# sofi_v7_main_rev2_2.net
KiCad netlist of a schematic drawn in EAGLE
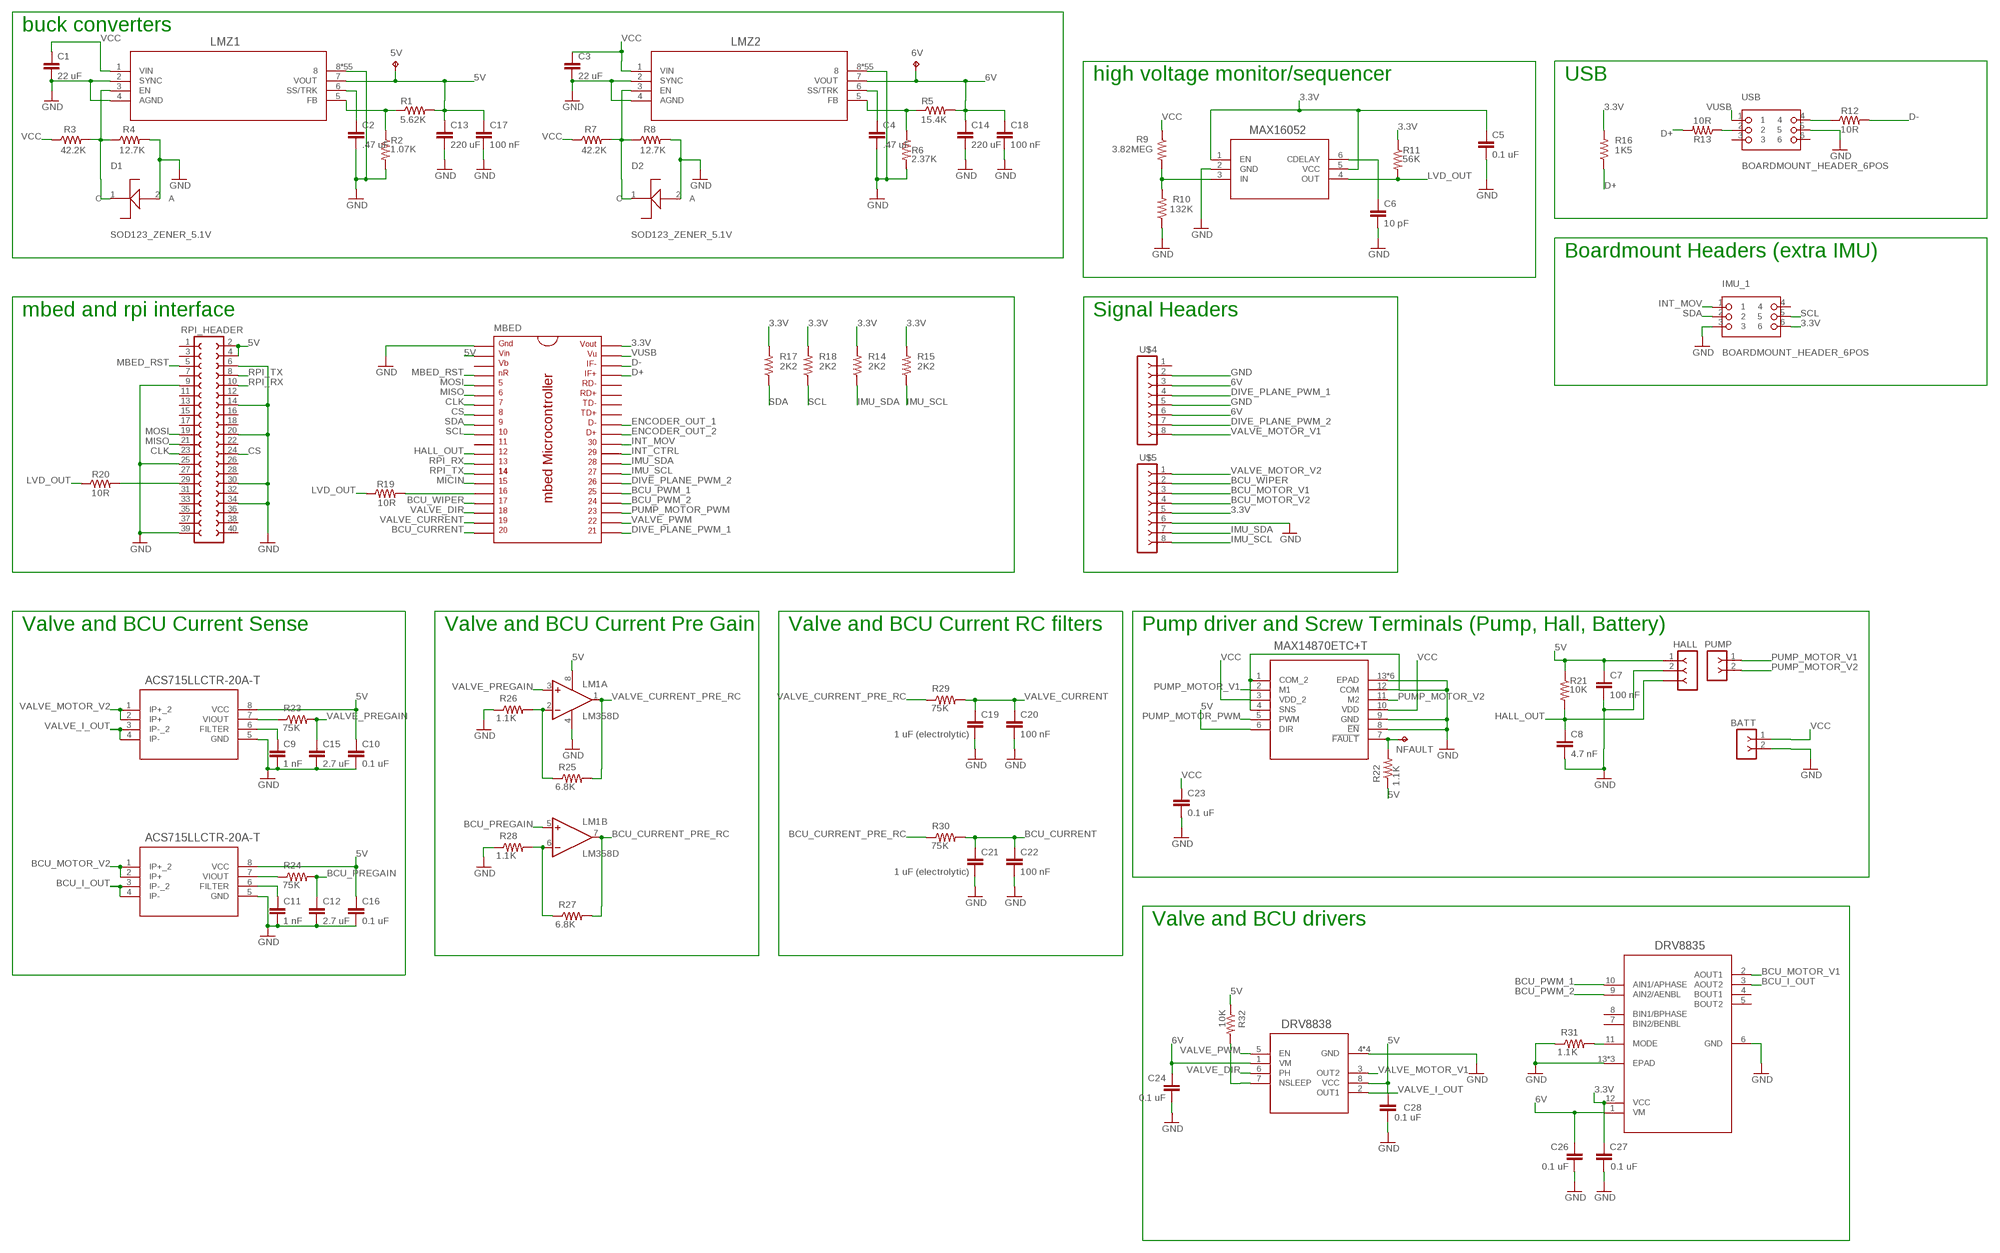
[diagram p0: schematic, sheet 1]

(export (version "E")
  (design (tool "Eeschema 10.0.6"))
  (components
    (comp (ref "5V")
      (value "TPB1,27")
      (footprint "eagle-import:B1,27")
      (libsource (lib "eagle-import") (part "TPB1,27"))
    )
    (comp (ref "6V")
      (value "TPB1,27")
      (footprint "eagle-import:B1,27")
      (libsource (lib "eagle-import") (part "TPB1,27"))
    )
    (comp (ref "ACS715_BCU")
      (value "ACS715LLCTR-20A-T")
      (footprint "eagle-import:SOIC-8")
      (fields (field (name "MANUFACTURER_PART_NUMBER") "ACS715LLCTR20AT"))
      (libsource (lib "eagle-import") (part "ACS715LLCTR-20A-T"))
    )
    (comp (ref "ACS715_VALVE")
      (value "ACS715LLCTR-20A-T")
      (footprint "eagle-import:SOIC-8")
      (fields (field (name "MANUFACTURER_PART_NUMBER") "ACS715LLCTR20AT"))
      (libsource (lib "eagle-import") (part "ACS715LLCTR-20A-T"))
    )
    (comp (ref "BATT")
      (value "2POS_BLOCK2POS_BLOCK_NOSTANDS")
      (footprint "eagle-import:2POS_BLOCK_NOSTANDS")
      (libsource (lib "eagle-import") (part "2POS_BLOCK2POS_BLOCK_NOSTANDS"))
    )
    (comp (ref "C1")
      (value "22 uF")
      (footprint "eagle-import:C0805")
      (libsource (lib "eagle-import") (part "C-EUC0805"))
    )
    (comp (ref "C2")
      (value ".47 uF")
      (footprint "eagle-import:C0805")
      (libsource (lib "eagle-import") (part "C-EUC0805"))
    )
    (comp (ref "C3")
      (value "22 uF")
      (footprint "eagle-import:C0805")
      (libsource (lib "eagle-import") (part "C-EUC0805"))
    )
    (comp (ref "C4")
      (value ".47 uF")
      (footprint "eagle-import:C0805")
      (libsource (lib "eagle-import") (part "C-EUC0805"))
    )
    (comp (ref "C5")
      (value "0.1 uF")
      (footprint "eagle-import:C0805")
      (libsource (lib "eagle-import") (part "C-EUC0805"))
    )
    (comp (ref "C6")
      (value "10 pF")
      (footprint "eagle-import:C0603")
      (libsource (lib "eagle-import") (part "C-EUC0603"))
    )
    (comp (ref "C7")
      (value "100 nF")
      (footprint "eagle-import:C0805")
      (libsource (lib "eagle-import") (part "C-EUC0805"))
    )
    (comp (ref "C8")
      (value "4.7 nF")
      (footprint "eagle-import:C0805")
      (libsource (lib "eagle-import") (part "C-EUC0805"))
    )
    (comp (ref "C9")
      (value "1 nF")
      (footprint "eagle-import:C0603")
      (libsource (lib "eagle-import") (part "C-EUC0603"))
    )
    (comp (ref "C10")
      (value "0.1 uF")
      (footprint "eagle-import:C0603")
      (libsource (lib "eagle-import") (part "C-EUC0603"))
    )
    (comp (ref "C11")
      (value "1 nF")
      (footprint "eagle-import:C0603")
      (libsource (lib "eagle-import") (part "C-EUC0603"))
    )
    (comp (ref "C12")
      (value "2.7 uF")
      (footprint "eagle-import:C0603")
      (libsource (lib "eagle-import") (part "C-EUC0603"))
    )
    (comp (ref "C13")
      (value "220 uF")
      (footprint "eagle-import:C1206")
      (libsource (lib "eagle-import") (part "resistor_C-EUC1206"))
    )
    (comp (ref "C14")
      (value "220 uF")
      (footprint "eagle-import:C1206")
      (libsource (lib "eagle-import") (part "resistor_C-EUC1206"))
    )
    (comp (ref "C15")
      (value "2.7 uF")
      (footprint "eagle-import:C0603")
      (libsource (lib "eagle-import") (part "C-EUC0603"))
    )
    (comp (ref "C16")
      (value "0.1 uF")
      (footprint "eagle-import:C0603")
      (libsource (lib "eagle-import") (part "C-EUC0603"))
    )
    (comp (ref "C17")
      (value "100 nF")
      (footprint "eagle-import:C0805")
      (libsource (lib "eagle-import") (part "C-EUC0805"))
    )
    (comp (ref "C18")
      (value "100 nF")
      (footprint "eagle-import:C0805")
      (libsource (lib "eagle-import") (part "C-EUC0805"))
    )
    (comp (ref "C19")
      (value "1 uF (electrolytic)")
      (footprint "eagle-import:C0603")
      (libsource (lib "eagle-import") (part "C-EUC0603"))
    )
    (comp (ref "C20")
      (value "100 nF")
      (footprint "eagle-import:C0805")
      (libsource (lib "eagle-import") (part "C-EUC0805"))
    )
    (comp (ref "C21")
      (value "1 uF (electrolytic)")
      (footprint "eagle-import:C0603")
      (libsource (lib "eagle-import") (part "C-EUC0603"))
    )
    (comp (ref "C22")
      (value "100 nF")
      (footprint "eagle-import:C0805")
      (libsource (lib "eagle-import") (part "C-EUC0805"))
    )
    (comp (ref "C23")
      (value "0.1 uF")
      (footprint "eagle-import:C0805")
      (libsource (lib "eagle-import") (part "C-EUC0805"))
    )
    (comp (ref "C24")
      (value "0.1 uF")
      (footprint "eagle-import:C0603")
      (libsource (lib "eagle-import") (part "C-EUC0603"))
    )
    (comp (ref "C26")
      (value "0.1 uF")
      (footprint "eagle-import:C0603")
      (libsource (lib "eagle-import") (part "C-EUC0603"))
    )
    (comp (ref "C27")
      (value "0.1 uF")
      (footprint "eagle-import:C0603")
      (libsource (lib "eagle-import") (part "C-EUC0603"))
    )
    (comp (ref "C28")
      (value "0.1 uF")
      (footprint "eagle-import:C0603")
      (libsource (lib "eagle-import") (part "C-EUC0603"))
    )
    (comp (ref "D1")
      (value "SOD123_ZENER_5.1V")
      (footprint "eagle-import:SOD123_ZENER")
      (libsource (lib "eagle-import") (part "SOD123_ZENER_5.1V"))
    )
    (comp (ref "D2")
      (value "SOD123_ZENER_5.1V")
      (footprint "eagle-import:SOD123_ZENER")
      (libsource (lib "eagle-import") (part "SOD123_ZENER_5.1V"))
    )
    (comp (ref "DRV8835")
      (value "DRV8835DSSRDSS12_P9X2_THERMAL_EXTENDED")
      (footprint "eagle-import:DSS12_P9X2_THERMAL_EXTENDED")
      (libsource (lib "eagle-import") (part "DRV8835DSSRDSS12_P9X2_THERMAL_EXTENDED"))
    )
    (comp (ref "DRV8838")
      (value "DRV8838DSGTDSG8_P9X1P6_THERMAL_EXTENDED")
      (footprint "eagle-import:DSG8_P9X1P6_THERMAL_EXTENDED")
      (libsource (lib "eagle-import") (part "DRV8838DSGTDSG8_P9X1P6_THERMAL_EXTENDED"))
    )
    (comp (ref "HALL")
      (value "3POS_TERMINAL")
      (footprint "eagle-import:3POS_TERMINAL")
      (libsource (lib "eagle-import") (part "3POS_TERMINAL"))
    )
    (comp (ref "IMU_1")
      (value "BOARDMOUNT_HEADER_6POS")
      (footprint "eagle-import:BOARDMOUNT_HEADER")
      (libsource (lib "eagle-import") (part "BOARDMOUNT_HEADER_6POS"))
    )
    (comp (ref "LM1")
      (value "LM358D")
      (footprint "eagle-import:SO08")
      (libsource (lib "eagle-import") (part "LM358D"))
    )
    (comp (ref "LMZ1")
      (value "LMZ23605TZE/NOPBTZA07A_THERMAL_TABBED")
      (footprint "eagle-import:TZA07A_THERMAL_TABBED")
      (libsource (lib "eagle-import") (part "LMZ23605TZE/NOPBTZA07A_THERMAL_TABBED"))
    )
    (comp (ref "LMZ2")
      (value "LMZ23605TZE/NOPBTZA07A_THERMAL_TABBED")
      (footprint "eagle-import:TZA07A_THERMAL_TABBED")
      (libsource (lib "eagle-import") (part "LMZ23605TZE/NOPBTZA07A_THERMAL_TABBED"))
    )
    (comp (ref "MAX14870")
      (value "MAX14870ETC+T")
      (footprint "eagle-import:21-0664B")
      (fields (field (name "COPYRIGHT") "Copyright (C) 2018 Accelerated Designs. All rights reserved"))
      (libsource (lib "eagle-import") (part "MAX14870ETC+T"))
    )
    (comp (ref "MAX16052")
      (value "MAX16052AUT+T")
      (footprint "eagle-import:21-0058I")
      (fields (field (name "MANUFACTURER_PART_NUMBER") "max16052aut+t"))
      (libsource (lib "eagle-import") (part "MAX16052AUT+T"))
    )
    (comp (ref "MBED")
      (value "MBED_MICROCONTROLLER")
      (footprint "eagle-import:DIL40_0.9")
      (libsource (lib "eagle-import") (part "MBED_MICROCONTROLLER"))
    )
    (comp (ref "NFAULT")
      (value "TPB1,27")
      (footprint "eagle-import:B1,27")
      (libsource (lib "eagle-import") (part "TPB1,27"))
    )
    (comp (ref "PUMP")
      (value "2POS_BLOCK2POS_BLOCK_NOSTANDS")
      (footprint "eagle-import:2POS_BLOCK_NOSTANDS")
      (libsource (lib "eagle-import") (part "2POS_BLOCK2POS_BLOCK_NOSTANDS"))
    )
    (comp (ref "R1")
      (value "5.62K")
      (footprint "eagle-import:M0805")
      (libsource (lib "eagle-import") (part "R-US_M0805"))
    )
    (comp (ref "R2")
      (value "1.07K")
      (footprint "eagle-import:M0805")
      (libsource (lib "eagle-import") (part "R-US_M0805"))
    )
    (comp (ref "R3")
      (value "42.2K")
      (footprint "eagle-import:M0805")
      (libsource (lib "eagle-import") (part "R-US_M0805"))
    )
    (comp (ref "R4")
      (value "12.7K")
      (footprint "eagle-import:M0805")
      (libsource (lib "eagle-import") (part "R-US_M0805"))
    )
    (comp (ref "R5")
      (value "15.4K")
      (footprint "eagle-import:M0805")
      (libsource (lib "eagle-import") (part "R-US_M0805"))
    )
    (comp (ref "R6")
      (value "2.37K")
      (footprint "eagle-import:M0805")
      (libsource (lib "eagle-import") (part "R-US_M0805"))
    )
    (comp (ref "R7")
      (value "42.2K")
      (footprint "eagle-import:M0805")
      (libsource (lib "eagle-import") (part "R-US_M0805"))
    )
    (comp (ref "R8")
      (value "12.7K")
      (footprint "eagle-import:M0805")
      (libsource (lib "eagle-import") (part "R-US_M0805"))
    )
    (comp (ref "R9")
      (value "3.82MEG")
      (footprint "eagle-import:0603")
      (libsource (lib "eagle-import") (part "RESISTOR0603"))
    )
    (comp (ref "R10")
      (value "132K")
      (footprint "eagle-import:0603")
      (libsource (lib "eagle-import") (part "RESISTOR0603"))
    )
    (comp (ref "R11")
      (value "56K")
      (footprint "eagle-import:R0603")
      (libsource (lib "eagle-import") (part "R-US_R0603"))
    )
    (comp (ref "R12")
      (value "10R")
      (footprint "eagle-import:0603")
      (libsource (lib "eagle-import") (part "RESISTOR0603"))
    )
    (comp (ref "R13")
      (value "10R")
      (footprint "eagle-import:0603")
      (libsource (lib "eagle-import") (part "RESISTOR0603"))
    )
    (comp (ref "R14")
      (value "2K2")
      (footprint "eagle-import:0603")
      (libsource (lib "eagle-import") (part "RESISTOR0603"))
    )
    (comp (ref "R15")
      (value "2K2")
      (footprint "eagle-import:0603")
      (libsource (lib "eagle-import") (part "RESISTOR0603"))
    )
    (comp (ref "R16")
      (value "1K5")
      (footprint "eagle-import:0603")
      (libsource (lib "eagle-import") (part "RESISTOR0603"))
    )
    (comp (ref "R17")
      (value "2K2")
      (footprint "eagle-import:0603")
      (libsource (lib "eagle-import") (part "RESISTOR0603"))
    )
    (comp (ref "R18")
      (value "2K2")
      (footprint "eagle-import:0603")
      (libsource (lib "eagle-import") (part "RESISTOR0603"))
    )
    (comp (ref "R19")
      (value "10R")
      (footprint "eagle-import:0603")
      (libsource (lib "eagle-import") (part "RESISTOR0603"))
    )
    (comp (ref "R20")
      (value "10R")
      (footprint "eagle-import:0603")
      (libsource (lib "eagle-import") (part "RESISTOR0603"))
    )
    (comp (ref "R21")
      (value "10K")
      (footprint "eagle-import:M0805")
      (libsource (lib "eagle-import") (part "R-US_M0805"))
    )
    (comp (ref "R22")
      (value "1.1K")
      (footprint "eagle-import:M0805")
      (libsource (lib "eagle-import") (part "R-US_M0805"))
    )
    (comp (ref "R23")
      (value "75K")
      (footprint "eagle-import:M0805")
      (libsource (lib "eagle-import") (part "R-US_M0805"))
    )
    (comp (ref "R24")
      (value "75K")
      (footprint "eagle-import:M0805")
      (libsource (lib "eagle-import") (part "R-US_M0805"))
    )
    (comp (ref "R25")
      (value "6.8K")
      (footprint "eagle-import:M0805")
      (libsource (lib "eagle-import") (part "R-US_M0805"))
    )
    (comp (ref "R26")
      (value "1.1K")
      (footprint "eagle-import:M0805")
      (libsource (lib "eagle-import") (part "R-US_M0805"))
    )
    (comp (ref "R27")
      (value "6.8K")
      (footprint "eagle-import:M0805")
      (libsource (lib "eagle-import") (part "R-US_M0805"))
    )
    (comp (ref "R28")
      (value "1.1K")
      (footprint "eagle-import:M0805")
      (libsource (lib "eagle-import") (part "R-US_M0805"))
    )
    (comp (ref "R29")
      (value "75K")
      (footprint "eagle-import:M0805")
      (libsource (lib "eagle-import") (part "R-US_M0805"))
    )
    (comp (ref "R30")
      (value "75K")
      (footprint "eagle-import:M0805")
      (libsource (lib "eagle-import") (part "R-US_M0805"))
    )
    (comp (ref "R31")
      (value "1.1K")
      (footprint "eagle-import:M0805")
      (libsource (lib "eagle-import") (part "R-US_M0805"))
    )
    (comp (ref "R32")
      (value "10K")
      (footprint "eagle-import:M0805")
      (libsource (lib "eagle-import") (part "R-US_M0805"))
    )
    (comp (ref "RPI_HEADER")
      (value "FE20-2")
      (footprint "eagle-import:FE20-2")
      (libsource (lib "eagle-import") (part "FE20-2"))
    )
    (comp (ref "U$4")
      (value "8POS_TERMINAL")
      (footprint "eagle-import:8POS_TERMINAL")
      (libsource (lib "eagle-import") (part "8POS_TERMINAL"))
    )
    (comp (ref "U$5")
      (value "8POS_TERMINAL")
      (footprint "eagle-import:8POS_TERMINAL")
      (libsource (lib "eagle-import") (part "8POS_TERMINAL"))
    )
    (comp (ref "USB")
      (value "BOARDMOUNT_HEADER_6POS")
      (footprint "eagle-import:BOARDMOUNT_HEADER")
      (libsource (lib "eagle-import") (part "BOARDMOUNT_HEADER_6POS"))
    )
  )
  (nets
    (net (code "1") (name "/3.3V") (class "Default")
      (node (ref "C27") (pin "1") (pinfunction "1_1") (pintype "passive"))
      (node (ref "C5") (pin "1") (pinfunction "1_1") (pintype "passive"))
      (node (ref "DRV8835") (pin "12") (pinfunction "VCC_12") (pintype "power_in"))
      (node (ref "IMU_1") (pin "6") (pinfunction "6_6") (pintype "bidirectional"))
      (node (ref "MAX16052") (pin "1") (pinfunction "EN_1") (pintype "input"))
      (node (ref "MAX16052") (pin "5") (pinfunction "VCC_5") (pintype "power_in"))
      (node (ref "MBED") (pin "40") (pinfunction "P$40_40") (pintype "bidirectional"))
      (node (ref "R11") (pin "1") (pinfunction "1_1") (pintype "passive"))
      (node (ref "R14") (pin "2") (pinfunction "2_2") (pintype "passive"))
      (node (ref "R15") (pin "2") (pinfunction "2_2") (pintype "passive"))
      (node (ref "R16") (pin "2") (pinfunction "2_2") (pintype "passive"))
      (node (ref "R17") (pin "2") (pinfunction "2_2") (pintype "passive"))
      (node (ref "R18") (pin "2") (pinfunction "2_2") (pintype "passive"))
      (node (ref "U$5") (pin "5") (pinfunction "5_5") (pintype "passive"))
    )
    (net (code "2") (name "/5V") (class "Default")
      (node (ref "5V") (pin "TP") (pinfunction "TP_TP") (pintype "input"))
      (node (ref "ACS715_BCU") (pin "8") (pinfunction "VCC_8") (pintype "power_in"))
      (node (ref "ACS715_VALVE") (pin "8") (pinfunction "VCC_8") (pintype "power_in"))
      (node (ref "C10") (pin "1") (pinfunction "1_1") (pintype "passive"))
      (node (ref "C13") (pin "1") (pinfunction "1_1") (pintype "passive"))
      (node (ref "C16") (pin "1") (pinfunction "1_1") (pintype "passive"))
      (node (ref "C17") (pin "1") (pinfunction "1_1") (pintype "passive"))
      (node (ref "C28") (pin "1") (pinfunction "1_1") (pintype "passive"))
      (node (ref "C7") (pin "1") (pinfunction "1_1") (pintype "passive"))
      (node (ref "DRV8838") (pin "8") (pinfunction "VCC_8") (pintype "power_in"))
      (node (ref "HALL") (pin "1") (pinfunction "1_1") (pintype "passive"))
      (node (ref "LM1") (pin "8") (pinfunction "V+_8") (pintype "power_in"))
      (node (ref "LMZ1") (pin "7") (pinfunction "VOUT_7") (pintype "output"))
      (node (ref "MAX14870") (pin "6") (pinfunction "DIR_6") (pintype "passive"))
      (node (ref "MBED") (pin "2") (pinfunction "P$2_2") (pintype "bidirectional"))
      (node (ref "R1") (pin "2") (pinfunction "2_2") (pintype "passive"))
      (node (ref "R21") (pin "1") (pinfunction "1_1") (pintype "passive"))
      (node (ref "R22") (pin "1") (pinfunction "1_1") (pintype "passive"))
      (node (ref "R32") (pin "1") (pinfunction "1_1") (pintype "passive"))
      (node (ref "RPI_HEADER") (pin "2") (pinfunction "2_2") (pintype "passive"))
      (node (ref "RPI_HEADER") (pin "4") (pinfunction "4_4") (pintype "passive"))
    )
    (net (code "3") (name "/6V") (class "Default")
      (node (ref "6V") (pin "TP") (pinfunction "TP_TP") (pintype "input"))
      (node (ref "C14") (pin "1") (pinfunction "1_1") (pintype "passive"))
      (node (ref "C18") (pin "1") (pinfunction "1_1") (pintype "passive"))
      (node (ref "C24") (pin "1") (pinfunction "1_1") (pintype "passive"))
      (node (ref "C26") (pin "1") (pinfunction "1_1") (pintype "passive"))
      (node (ref "DRV8835") (pin "1") (pinfunction "VM_1") (pintype "power_in"))
      (node (ref "DRV8838") (pin "1") (pinfunction "VM_1") (pintype "power_in"))
      (node (ref "LMZ2") (pin "7") (pinfunction "VOUT_7") (pintype "output"))
      (node (ref "R5") (pin "2") (pinfunction "2_2") (pintype "passive"))
      (node (ref "U$4") (pin "3") (pinfunction "3_3") (pintype "passive"))
      (node (ref "U$4") (pin "6") (pinfunction "6_6") (pintype "passive"))
    )
    (net (code "4") (name "/BCU_CURRENT") (class "Default")
      (node (ref "C21") (pin "1") (pinfunction "1_1") (pintype "passive"))
      (node (ref "C22") (pin "1") (pinfunction "1_1") (pintype "passive"))
      (node (ref "MBED") (pin "20") (pinfunction "P$20_20") (pintype "bidirectional"))
      (node (ref "R30") (pin "2") (pinfunction "2_2") (pintype "passive"))
    )
    (net (code "5") (name "/BCU_CURRENT_PRE_RC") (class "Default")
      (node (ref "LM1") (pin "7") (pinfunction "OUT_7") (pintype "output"))
      (node (ref "R27") (pin "2") (pinfunction "2_2") (pintype "passive"))
      (node (ref "R30") (pin "1") (pinfunction "1_1") (pintype "passive"))
    )
    (net (code "6") (name "/BCU_I_OUT") (class "Default")
      (node (ref "ACS715_BCU") (pin "3") (pinfunction "IP-_2_3") (pintype "output"))
      (node (ref "ACS715_BCU") (pin "4") (pinfunction "IP-_4") (pintype "output"))
      (node (ref "DRV8835") (pin "3") (pinfunction "AOUT2_3") (pintype "output"))
    )
    (net (code "7") (name "/BCU_MOTOR_V1") (class "Default")
      (node (ref "DRV8835") (pin "2") (pinfunction "AOUT1_2") (pintype "output"))
      (node (ref "U$5") (pin "3") (pinfunction "3_3") (pintype "passive"))
    )
    (net (code "8") (name "/BCU_MOTOR_V2") (class "Default")
      (node (ref "ACS715_BCU") (pin "1") (pinfunction "IP+_2_1") (pintype "input"))
      (node (ref "ACS715_BCU") (pin "2") (pinfunction "IP+_2") (pintype "input"))
      (node (ref "U$5") (pin "4") (pinfunction "4_4") (pintype "passive"))
    )
    (net (code "9") (name "/BCU_PREGAIN") (class "Default")
      (node (ref "C12") (pin "1") (pinfunction "1_1") (pintype "passive"))
      (node (ref "LM1") (pin "5") (pinfunction "+IN_5") (pintype "input"))
      (node (ref "R24") (pin "2") (pinfunction "2_2") (pintype "passive"))
    )
    (net (code "10") (name "/BCU_PWM_1") (class "Default")
      (node (ref "DRV8835") (pin "10") (pinfunction "AIN1/APHASE_10") (pintype "input"))
      (node (ref "MBED") (pin "25") (pinfunction "P$25_25") (pintype "bidirectional"))
    )
    (net (code "11") (name "/BCU_PWM_2") (class "Default")
      (node (ref "DRV8835") (pin "9") (pinfunction "AIN2/AENBL_9") (pintype "input"))
      (node (ref "MBED") (pin "24") (pinfunction "P$24_24") (pintype "bidirectional"))
    )
    (net (code "12") (name "/BCU_WIPER") (class "Default")
      (node (ref "MBED") (pin "17") (pinfunction "P$17_17") (pintype "bidirectional"))
      (node (ref "U$5") (pin "2") (pinfunction "2_2") (pintype "passive"))
    )
    (net (code "13") (name "/CLK") (class "Default")
      (node (ref "MBED") (pin "7") (pinfunction "P$7_7") (pintype "bidirectional"))
      (node (ref "RPI_HEADER") (pin "23") (pinfunction "23_23") (pintype "passive"))
    )
    (net (code "14") (name "/CS") (class "Default")
      (node (ref "MBED") (pin "8") (pinfunction "P$8_8") (pintype "bidirectional"))
      (node (ref "RPI_HEADER") (pin "24") (pinfunction "24_24") (pintype "passive"))
    )
    (net (code "15") (name "/D+") (class "Default")
      (node (ref "MBED") (pin "37") (pinfunction "P$37_37") (pintype "bidirectional"))
      (node (ref "R13") (pin "2") (pinfunction "2_2") (pintype "passive"))
      (node (ref "R16") (pin "1") (pinfunction "1_1") (pintype "passive"))
    )
    (net (code "16") (name "/D-") (class "Default")
      (node (ref "MBED") (pin "38") (pinfunction "P$38_38") (pintype "bidirectional"))
      (node (ref "R12") (pin "2") (pinfunction "2_2") (pintype "passive"))
    )
    (net (code "17") (name "/DIVE_PLANE_PWM_1") (class "Default")
      (node (ref "MBED") (pin "21") (pinfunction "P$21_21") (pintype "bidirectional"))
      (node (ref "U$4") (pin "4") (pinfunction "4_4") (pintype "passive"))
    )
    (net (code "18") (name "/DIVE_PLANE_PWM_2") (class "Default")
      (node (ref "MBED") (pin "26") (pinfunction "P$26_26") (pintype "bidirectional"))
      (node (ref "U$4") (pin "7") (pinfunction "7_7") (pintype "passive"))
    )
    (net (code "19") (name "/ENCODER_OUT_1") (class "Default")
      (node (ref "MBED") (pin "32") (pinfunction "P$32_32") (pintype "bidirectional"))
    )
    (net (code "20") (name "/ENCODER_OUT_2") (class "Default")
      (node (ref "MBED") (pin "31") (pinfunction "P$31_31") (pintype "bidirectional"))
    )
    (net (code "21") (name "/HALL_OUT") (class "Default")
      (node (ref "C8") (pin "1") (pinfunction "1_1") (pintype "passive"))
      (node (ref "HALL") (pin "3") (pinfunction "3_3") (pintype "passive"))
      (node (ref "MBED") (pin "12") (pinfunction "P$12_12") (pintype "bidirectional"))
      (node (ref "R21") (pin "2") (pinfunction "2_2") (pintype "passive"))
    )
    (net (code "22") (name "/IMU_SCL") (class "Default")
      (node (ref "MBED") (pin "27") (pinfunction "P$27_27") (pintype "bidirectional"))
      (node (ref "R15") (pin "1") (pinfunction "1_1") (pintype "passive"))
      (node (ref "U$5") (pin "8") (pinfunction "8_8") (pintype "passive"))
    )
    (net (code "23") (name "/IMU_SDA") (class "Default")
      (node (ref "MBED") (pin "28") (pinfunction "P$28_28") (pintype "bidirectional"))
      (node (ref "R14") (pin "1") (pinfunction "1_1") (pintype "passive"))
      (node (ref "U$5") (pin "7") (pinfunction "7_7") (pintype "passive"))
    )
    (net (code "24") (name "/INT_CTRL") (class "Default")
      (node (ref "MBED") (pin "29") (pinfunction "P$29_29") (pintype "bidirectional"))
    )
    (net (code "25") (name "/INT_MOV") (class "Default")
      (node (ref "IMU_1") (pin "1") (pinfunction "1_1") (pintype "bidirectional"))
      (node (ref "MBED") (pin "30") (pinfunction "P$30_30") (pintype "bidirectional"))
    )
    (net (code "26") (name "/LVD_OUT") (class "Default")
      (node (ref "MAX16052") (pin "4") (pinfunction "OUT_4") (pintype "output"))
      (node (ref "R11") (pin "2") (pinfunction "2_2") (pintype "passive"))
      (node (ref "R19") (pin "1") (pinfunction "1_1") (pintype "passive"))
      (node (ref "R20") (pin "1") (pinfunction "1_1") (pintype "passive"))
    )
    (net (code "27") (name "/MBED_RST") (class "Default")
      (node (ref "MBED") (pin "4") (pinfunction "P$4_4") (pintype "bidirectional"))
      (node (ref "RPI_HEADER") (pin "5") (pinfunction "5_5") (pintype "passive"))
    )
    (net (code "28") (name "/MICIN") (class "Default")
      (node (ref "MBED") (pin "15") (pinfunction "P$15_15") (pintype "bidirectional"))
    )
    (net (code "29") (name "/MISO") (class "Default")
      (node (ref "MBED") (pin "6") (pinfunction "P$6_6") (pintype "bidirectional"))
      (node (ref "RPI_HEADER") (pin "21") (pinfunction "21_21") (pintype "passive"))
    )
    (net (code "30") (name "/MOSI") (class "Default")
      (node (ref "MBED") (pin "5") (pinfunction "P$5_5") (pintype "bidirectional"))
      (node (ref "RPI_HEADER") (pin "19") (pinfunction "19_19") (pintype "passive"))
    )
    (net (code "31") (name "/PUMP_MOTOR_PWM") (class "Default")
      (node (ref "MAX14870") (pin "5") (pinfunction "PWM_5") (pintype "passive"))
      (node (ref "MBED") (pin "23") (pinfunction "P$23_23") (pintype "bidirectional"))
    )
    (net (code "32") (name "/PUMP_MOTOR_V1") (class "Default")
      (node (ref "MAX14870") (pin "2") (pinfunction "M1_2") (pintype "bidirectional"))
      (node (ref "PUMP") (pin "1") (pinfunction "1_1") (pintype "passive"))
    )
    (net (code "33") (name "/PUMP_MOTOR_V2") (class "Default")
      (node (ref "MAX14870") (pin "11") (pinfunction "M2_11") (pintype "bidirectional"))
      (node (ref "PUMP") (pin "2") (pinfunction "2_2") (pintype "passive"))
    )
    (net (code "34") (name "/RPI_RX") (class "Default")
      (node (ref "MBED") (pin "13") (pinfunction "P$13_13") (pintype "bidirectional"))
      (node (ref "RPI_HEADER") (pin "10") (pinfunction "10_10") (pintype "passive"))
    )
    (net (code "35") (name "/RPI_TX") (class "Default")
      (node (ref "MBED") (pin "14") (pinfunction "P$14_14") (pintype "bidirectional"))
      (node (ref "RPI_HEADER") (pin "8") (pinfunction "8_8") (pintype "passive"))
    )
    (net (code "36") (name "/SCL") (class "Default")
      (node (ref "IMU_1") (pin "5") (pinfunction "5_5") (pintype "bidirectional"))
      (node (ref "MBED") (pin "10") (pinfunction "P$10_10") (pintype "bidirectional"))
      (node (ref "R18") (pin "1") (pinfunction "1_1") (pintype "passive"))
    )
    (net (code "37") (name "/SDA") (class "Default")
      (node (ref "IMU_1") (pin "2") (pinfunction "2_2") (pintype "bidirectional"))
      (node (ref "MBED") (pin "9") (pinfunction "P$9_9") (pintype "bidirectional"))
      (node (ref "R17") (pin "1") (pinfunction "1_1") (pintype "passive"))
    )
    (net (code "38") (name "/VALVE_CURRENT") (class "Default")
      (node (ref "C19") (pin "1") (pinfunction "1_1") (pintype "passive"))
      (node (ref "C20") (pin "1") (pinfunction "1_1") (pintype "passive"))
      (node (ref "MBED") (pin "19") (pinfunction "P$19_19") (pintype "bidirectional"))
      (node (ref "R29") (pin "2") (pinfunction "2_2") (pintype "passive"))
    )
    (net (code "39") (name "/VALVE_CURRENT_PRE_RC") (class "Default")
      (node (ref "LM1") (pin "1") (pinfunction "OUT_1") (pintype "output"))
      (node (ref "R25") (pin "2") (pinfunction "2_2") (pintype "passive"))
      (node (ref "R29") (pin "1") (pinfunction "1_1") (pintype "passive"))
    )
    (net (code "40") (name "/VALVE_DIR") (class "Default")
      (node (ref "DRV8838") (pin "6") (pinfunction "PH_6") (pintype "input"))
      (node (ref "MBED") (pin "18") (pinfunction "P$18_18") (pintype "bidirectional"))
    )
    (net (code "41") (name "/VALVE_I_OUT") (class "Default")
      (node (ref "ACS715_VALVE") (pin "3") (pinfunction "IP-_2_3") (pintype "output"))
      (node (ref "ACS715_VALVE") (pin "4") (pinfunction "IP-_4") (pintype "output"))
      (node (ref "DRV8838") (pin "2") (pinfunction "OUT1_2") (pintype "output"))
    )
    (net (code "42") (name "/VALVE_MOTOR_V1") (class "Default")
      (node (ref "DRV8838") (pin "3") (pinfunction "OUT2_3") (pintype "output"))
      (node (ref "U$4") (pin "8") (pinfunction "8_8") (pintype "passive"))
    )
    (net (code "43") (name "/VALVE_MOTOR_V2") (class "Default")
      (node (ref "ACS715_VALVE") (pin "1") (pinfunction "IP+_2_1") (pintype "input"))
      (node (ref "ACS715_VALVE") (pin "2") (pinfunction "IP+_2") (pintype "input"))
      (node (ref "U$5") (pin "1") (pinfunction "1_1") (pintype "passive"))
    )
    (net (code "44") (name "/VALVE_PREGAIN") (class "Default")
      (node (ref "C15") (pin "1") (pinfunction "1_1") (pintype "passive"))
      (node (ref "LM1") (pin "3") (pinfunction "+IN_3") (pintype "input"))
      (node (ref "R23") (pin "2") (pinfunction "2_2") (pintype "passive"))
    )
    (net (code "45") (name "/VALVE_PWM") (class "Default")
      (node (ref "DRV8838") (pin "5") (pinfunction "EN_5") (pintype "input"))
      (node (ref "MBED") (pin "22") (pinfunction "P$22_22") (pintype "bidirectional"))
    )
    (net (code "46") (name "/VCC") (class "Default")
      (node (ref "BATT") (pin "1") (pinfunction "1_1") (pintype "passive"))
      (node (ref "C1") (pin "1") (pinfunction "1_1") (pintype "passive"))
      (node (ref "C23") (pin "1") (pinfunction "1_1") (pintype "passive"))
      (node (ref "C3") (pin "1") (pinfunction "1_1") (pintype "passive"))
      (node (ref "LMZ1") (pin "1") (pinfunction "VIN_1") (pintype "input"))
      (node (ref "LMZ2") (pin "1") (pinfunction "VIN_1") (pintype "input"))
      (node (ref "MAX14870") (pin "10") (pinfunction "VDD_10") (pintype "power_in"))
      (node (ref "MAX14870") (pin "3") (pinfunction "VDD_2_3") (pintype "power_in"))
      (node (ref "R3") (pin "1") (pinfunction "1_1") (pintype "passive"))
      (node (ref "R7") (pin "1") (pinfunction "1_1") (pintype "passive"))
      (node (ref "R9") (pin "1") (pinfunction "1_1") (pintype "passive"))
    )
    (net (code "47") (name "/VUSB") (class "Default")
      (node (ref "MBED") (pin "39") (pinfunction "P$39_39") (pintype "bidirectional"))
      (node (ref "USB") (pin "1") (pinfunction "1_1") (pintype "bidirectional"))
    )
    (net (code "48") (name "GND") (class "Default")
      (node (ref "ACS715_BCU") (pin "5") (pinfunction "GND_5") (pintype "power_in"))
      (node (ref "ACS715_VALVE") (pin "5") (pinfunction "GND_5") (pintype "power_in"))
      (node (ref "BATT") (pin "2") (pinfunction "2_2") (pintype "passive"))
      (node (ref "C1") (pin "2") (pinfunction "2_2") (pintype "passive"))
      (node (ref "C10") (pin "2") (pinfunction "2_2") (pintype "passive"))
      (node (ref "C11") (pin "2") (pinfunction "2_2") (pintype "passive"))
      (node (ref "C12") (pin "2") (pinfunction "2_2") (pintype "passive"))
      (node (ref "C13") (pin "2") (pinfunction "2_2") (pintype "passive"))
      (node (ref "C14") (pin "2") (pinfunction "2_2") (pintype "passive"))
      (node (ref "C15") (pin "2") (pinfunction "2_2") (pintype "passive"))
      (node (ref "C16") (pin "2") (pinfunction "2_2") (pintype "passive"))
      (node (ref "C17") (pin "2") (pinfunction "2_2") (pintype "passive"))
      (node (ref "C18") (pin "2") (pinfunction "2_2") (pintype "passive"))
      (node (ref "C19") (pin "2") (pinfunction "2_2") (pintype "passive"))
      (node (ref "C2") (pin "2") (pinfunction "2_2") (pintype "passive"))
      (node (ref "C20") (pin "2") (pinfunction "2_2") (pintype "passive"))
      (node (ref "C21") (pin "2") (pinfunction "2_2") (pintype "passive"))
      (node (ref "C22") (pin "2") (pinfunction "2_2") (pintype "passive"))
      (node (ref "C23") (pin "2") (pinfunction "2_2") (pintype "passive"))
      (node (ref "C24") (pin "2") (pinfunction "2_2") (pintype "passive"))
      (node (ref "C26") (pin "2") (pinfunction "2_2") (pintype "passive"))
      (node (ref "C27") (pin "2") (pinfunction "2_2") (pintype "passive"))
      (node (ref "C28") (pin "2") (pinfunction "2_2") (pintype "passive"))
      (node (ref "C3") (pin "2") (pinfunction "2_2") (pintype "passive"))
      (node (ref "C4") (pin "2") (pinfunction "2_2") (pintype "passive"))
      (node (ref "C5") (pin "2") (pinfunction "2_2") (pintype "passive"))
      (node (ref "C6") (pin "2") (pinfunction "2_2") (pintype "passive"))
      (node (ref "C7") (pin "2") (pinfunction "2_2") (pintype "passive"))
      (node (ref "C8") (pin "2") (pinfunction "2_2") (pintype "passive"))
      (node (ref "C9") (pin "2") (pinfunction "2_2") (pintype "passive"))
      (node (ref "D1") (pin "2") (pinfunction "A_2") (pintype "bidirectional"))
      (node (ref "D2") (pin "2") (pinfunction "A_2") (pintype "bidirectional"))
      (node (ref "DRV8835") (pin "13") (pinfunction "EPAD_13") (pintype "passive"))
      (node (ref "DRV8835") (pin "6") (pinfunction "GND_6") (pintype "power_in"))
      (node (ref "DRV8835") (pin "P$1") (pinfunction "EPAD_P$1") (pintype "passive"))
      (node (ref "DRV8835") (pin "P$2") (pinfunction "EPAD_P$2") (pintype "passive"))
      (node (ref "DRV8838") (pin "4") (pinfunction "GND_4") (pintype "power_in"))
      (node (ref "DRV8838") (pin "9") (pinfunction "GND_9") (pintype "power_in"))
      (node (ref "DRV8838") (pin "P$1") (pinfunction "GND_P$1") (pintype "power_in"))
      (node (ref "DRV8838") (pin "P$2") (pinfunction "GND_P$2") (pintype "power_in"))
      (node (ref "HALL") (pin "2") (pinfunction "2_2") (pintype "passive"))
      (node (ref "IMU_1") (pin "3") (pinfunction "3_3") (pintype "bidirectional"))
      (node (ref "LM1") (pin "4") (pinfunction "V-_4") (pintype "power_in"))
      (node (ref "LMZ1") (pin "2") (pinfunction "SYNC_2") (pintype "input"))
      (node (ref "LMZ1") (pin "4") (pinfunction "AGND_4") (pintype "power_in"))
      (node (ref "LMZ1") (pin "8") (pinfunction "8_8") (pintype "passive"))
      (node (ref "LMZ1") (pin "P$1") (pinfunction "8_P$1") (pintype "passive"))
      (node (ref "LMZ1") (pin "P$10") (pinfunction "8_P$10") (pintype "passive"))
      (node (ref "LMZ1") (pin "P$11") (pinfunction "8_P$11") (pintype "passive"))
      (node (ref "LMZ1") (pin "P$12") (pinfunction "8_P$12") (pintype "passive"))
      (node (ref "LMZ1") (pin "P$13") (pinfunction "8_P$13") (pintype "passive"))
      (node (ref "LMZ1") (pin "P$14") (pinfunction "8_P$14") (pintype "passive"))
      (node (ref "LMZ1") (pin "P$15") (pinfunction "8_P$15") (pintype "passive"))
      (node (ref "LMZ1") (pin "P$16") (pinfunction "8_P$16") (pintype "passive"))
      (node (ref "LMZ1") (pin "P$17") (pinfunction "8_P$17") (pintype "passive"))
      (node (ref "LMZ1") (pin "P$18") (pinfunction "8_P$18") (pintype "passive"))
      (node (ref "LMZ1") (pin "P$19") (pinfunction "8_P$19") (pintype "passive"))
      (node (ref "LMZ1") (pin "P$2") (pinfunction "8_P$2") (pintype "passive"))
      (node (ref "LMZ1") (pin "P$20") (pinfunction "8_P$20") (pintype "passive"))
      (node (ref "LMZ1") (pin "P$21") (pinfunction "8_P$21") (pintype "passive"))
      (node (ref "LMZ1") (pin "P$22") (pinfunction "8_P$22") (pintype "passive"))
      (node (ref "LMZ1") (pin "P$23") (pinfunction "8_P$23") (pintype "passive"))
      (node (ref "LMZ1") (pin "P$24") (pinfunction "8_P$24") (pintype "passive"))
      (node (ref "LMZ1") (pin "P$25") (pinfunction "8_P$25") (pintype "passive"))
      (node (ref "LMZ1") (pin "P$26") (pinfunction "8_P$26") (pintype "passive"))
      (node (ref "LMZ1") (pin "P$27") (pinfunction "8_P$27") (pintype "passive"))
      (node (ref "LMZ1") (pin "P$28") (pinfunction "8_P$28") (pintype "passive"))
      (node (ref "LMZ1") (pin "P$29") (pinfunction "8_P$29") (pintype "passive"))
      (node (ref "LMZ1") (pin "P$3") (pinfunction "8_P$3") (pintype "passive"))
      (node (ref "LMZ1") (pin "P$30") (pinfunction "8_P$30") (pintype "passive"))
      (node (ref "LMZ1") (pin "P$31") (pinfunction "8_P$31") (pintype "passive"))
      (node (ref "LMZ1") (pin "P$32") (pinfunction "8_P$32") (pintype "passive"))
      (node (ref "LMZ1") (pin "P$33") (pinfunction "8_P$33") (pintype "passive"))
      (node (ref "LMZ1") (pin "P$34") (pinfunction "8_P$34") (pintype "passive"))
      (node (ref "LMZ1") (pin "P$35") (pinfunction "8_P$35") (pintype "passive"))
      (node (ref "LMZ1") (pin "P$36") (pinfunction "8_P$36") (pintype "passive"))
      (node (ref "LMZ1") (pin "P$37") (pinfunction "8_P$37") (pintype "passive"))
      (node (ref "LMZ1") (pin "P$38") (pinfunction "8_P$38") (pintype "passive"))
      (node (ref "LMZ1") (pin "P$39") (pinfunction "8_P$39") (pintype "passive"))
      (node (ref "LMZ1") (pin "P$4") (pinfunction "8_P$4") (pintype "passive"))
      (node (ref "LMZ1") (pin "P$40") (pinfunction "8_P$40") (pintype "passive"))
      (node (ref "LMZ1") (pin "P$41") (pinfunction "8_P$41") (pintype "passive"))
      (node (ref "LMZ1") (pin "P$42") (pinfunction "8_P$42") (pintype "passive"))
      (node (ref "LMZ1") (pin "P$43") (pinfunction "8_P$43") (pintype "passive"))
      (node (ref "LMZ1") (pin "P$44") (pinfunction "8_P$44") (pintype "passive"))
      (node (ref "LMZ1") (pin "P$45") (pinfunction "8_P$45") (pintype "passive"))
      (node (ref "LMZ1") (pin "P$46") (pinfunction "8_P$46") (pintype "passive"))
      (node (ref "LMZ1") (pin "P$47") (pinfunction "8_P$47") (pintype "passive"))
      (node (ref "LMZ1") (pin "P$48") (pinfunction "8_P$48") (pintype "passive"))
      (node (ref "LMZ1") (pin "P$49") (pinfunction "8_P$49") (pintype "passive"))
      (node (ref "LMZ1") (pin "P$5") (pinfunction "8_P$5") (pintype "passive"))
      (node (ref "LMZ1") (pin "P$50") (pinfunction "8_P$50") (pintype "passive"))
      (node (ref "LMZ1") (pin "P$51") (pinfunction "8_P$51") (pintype "passive"))
      (node (ref "LMZ1") (pin "P$52") (pinfunction "8_P$52") (pintype "passive"))
      (node (ref "LMZ1") (pin "P$53") (pinfunction "8_P$53") (pintype "passive"))
      (node (ref "LMZ1") (pin "P$54") (pinfunction "8_P$54") (pintype "passive"))
      (node (ref "LMZ1") (pin "P$6") (pinfunction "8_P$6") (pintype "passive"))
      (node (ref "LMZ1") (pin "P$7") (pinfunction "8_P$7") (pintype "passive"))
      (node (ref "LMZ1") (pin "P$8") (pinfunction "8_P$8") (pintype "passive"))
      (node (ref "LMZ1") (pin "P$9") (pinfunction "8_P$9") (pintype "passive"))
      (node (ref "LMZ2") (pin "2") (pinfunction "SYNC_2") (pintype "input"))
      (node (ref "LMZ2") (pin "4") (pinfunction "AGND_4") (pintype "power_in"))
      (node (ref "LMZ2") (pin "8") (pinfunction "8_8") (pintype "passive"))
      (node (ref "LMZ2") (pin "P$1") (pinfunction "8_P$1") (pintype "passive"))
      (node (ref "LMZ2") (pin "P$10") (pinfunction "8_P$10") (pintype "passive"))
      (node (ref "LMZ2") (pin "P$11") (pinfunction "8_P$11") (pintype "passive"))
      (node (ref "LMZ2") (pin "P$12") (pinfunction "8_P$12") (pintype "passive"))
      (node (ref "LMZ2") (pin "P$13") (pinfunction "8_P$13") (pintype "passive"))
      (node (ref "LMZ2") (pin "P$14") (pinfunction "8_P$14") (pintype "passive"))
      (node (ref "LMZ2") (pin "P$15") (pinfunction "8_P$15") (pintype "passive"))
      (node (ref "LMZ2") (pin "P$16") (pinfunction "8_P$16") (pintype "passive"))
      (node (ref "LMZ2") (pin "P$17") (pinfunction "8_P$17") (pintype "passive"))
      (node (ref "LMZ2") (pin "P$18") (pinfunction "8_P$18") (pintype "passive"))
      (node (ref "LMZ2") (pin "P$19") (pinfunction "8_P$19") (pintype "passive"))
      (node (ref "LMZ2") (pin "P$2") (pinfunction "8_P$2") (pintype "passive"))
      (node (ref "LMZ2") (pin "P$20") (pinfunction "8_P$20") (pintype "passive"))
      (node (ref "LMZ2") (pin "P$21") (pinfunction "8_P$21") (pintype "passive"))
      (node (ref "LMZ2") (pin "P$22") (pinfunction "8_P$22") (pintype "passive"))
      (node (ref "LMZ2") (pin "P$23") (pinfunction "8_P$23") (pintype "passive"))
      (node (ref "LMZ2") (pin "P$24") (pinfunction "8_P$24") (pintype "passive"))
      (node (ref "LMZ2") (pin "P$25") (pinfunction "8_P$25") (pintype "passive"))
      (node (ref "LMZ2") (pin "P$26") (pinfunction "8_P$26") (pintype "passive"))
      (node (ref "LMZ2") (pin "P$27") (pinfunction "8_P$27") (pintype "passive"))
      (node (ref "LMZ2") (pin "P$28") (pinfunction "8_P$28") (pintype "passive"))
      (node (ref "LMZ2") (pin "P$29") (pinfunction "8_P$29") (pintype "passive"))
      (node (ref "LMZ2") (pin "P$3") (pinfunction "8_P$3") (pintype "passive"))
      (node (ref "LMZ2") (pin "P$30") (pinfunction "8_P$30") (pintype "passive"))
      (node (ref "LMZ2") (pin "P$31") (pinfunction "8_P$31") (pintype "passive"))
      (node (ref "LMZ2") (pin "P$32") (pinfunction "8_P$32") (pintype "passive"))
      (node (ref "LMZ2") (pin "P$33") (pinfunction "8_P$33") (pintype "passive"))
      (node (ref "LMZ2") (pin "P$34") (pinfunction "8_P$34") (pintype "passive"))
      (node (ref "LMZ2") (pin "P$35") (pinfunction "8_P$35") (pintype "passive"))
      (node (ref "LMZ2") (pin "P$36") (pinfunction "8_P$36") (pintype "passive"))
      (node (ref "LMZ2") (pin "P$37") (pinfunction "8_P$37") (pintype "passive"))
      (node (ref "LMZ2") (pin "P$38") (pinfunction "8_P$38") (pintype "passive"))
      (node (ref "LMZ2") (pin "P$39") (pinfunction "8_P$39") (pintype "passive"))
      (node (ref "LMZ2") (pin "P$4") (pinfunction "8_P$4") (pintype "passive"))
      (node (ref "LMZ2") (pin "P$40") (pinfunction "8_P$40") (pintype "passive"))
      (node (ref "LMZ2") (pin "P$41") (pinfunction "8_P$41") (pintype "passive"))
      (node (ref "LMZ2") (pin "P$42") (pinfunction "8_P$42") (pintype "passive"))
      (node (ref "LMZ2") (pin "P$43") (pinfunction "8_P$43") (pintype "passive"))
      (node (ref "LMZ2") (pin "P$44") (pinfunction "8_P$44") (pintype "passive"))
      (node (ref "LMZ2") (pin "P$45") (pinfunction "8_P$45") (pintype "passive"))
      (node (ref "LMZ2") (pin "P$46") (pinfunction "8_P$46") (pintype "passive"))
      (node (ref "LMZ2") (pin "P$47") (pinfunction "8_P$47") (pintype "passive"))
      (node (ref "LMZ2") (pin "P$48") (pinfunction "8_P$48") (pintype "passive"))
      (node (ref "LMZ2") (pin "P$49") (pinfunction "8_P$49") (pintype "passive"))
      (node (ref "LMZ2") (pin "P$5") (pinfunction "8_P$5") (pintype "passive"))
      (node (ref "LMZ2") (pin "P$50") (pinfunction "8_P$50") (pintype "passive"))
      (node (ref "LMZ2") (pin "P$51") (pinfunction "8_P$51") (pintype "passive"))
      (node (ref "LMZ2") (pin "P$52") (pinfunction "8_P$52") (pintype "passive"))
      (node (ref "LMZ2") (pin "P$53") (pinfunction "8_P$53") (pintype "passive"))
      (node (ref "LMZ2") (pin "P$54") (pinfunction "8_P$54") (pintype "passive"))
      (node (ref "LMZ2") (pin "P$6") (pinfunction "8_P$6") (pintype "passive"))
      (node (ref "LMZ2") (pin "P$7") (pinfunction "8_P$7") (pintype "passive"))
      (node (ref "LMZ2") (pin "P$8") (pinfunction "8_P$8") (pintype "passive"))
      (node (ref "LMZ2") (pin "P$9") (pinfunction "8_P$9") (pintype "passive"))
      (node (ref "MAX14870") (pin "1") (pinfunction "COM_2_1") (pintype "passive"))
      (node (ref "MAX14870") (pin "12") (pinfunction "COM_12") (pintype "passive"))
      (node (ref "MAX14870") (pin "13") (pinfunction "EPAD_13") (pintype "passive"))
      (node (ref "MAX14870") (pin "14") (pinfunction "EPAD_14") (pintype "passive"))
      (node (ref "MAX14870") (pin "15") (pinfunction "EPAD_15") (pintype "passive"))
      (node (ref "MAX14870") (pin "16") (pinfunction "EPAD_16") (pintype "passive"))
      (node (ref "MAX14870") (pin "17") (pinfunction "EPAD_17") (pintype "passive"))
      (node (ref "MAX14870") (pin "18") (pinfunction "EPAD_18") (pintype "passive"))
      (node (ref "MAX14870") (pin "4") (pinfunction "SNS_4") (pintype "passive"))
      (node (ref "MAX14870") (pin "8") (pinfunction "~{EN}_8") (pintype "passive"))
      (node (ref "MAX14870") (pin "9") (pinfunction "GND_9") (pintype "passive"))
      (node (ref "MAX16052") (pin "2") (pinfunction "GND_2") (pintype "power_in"))
      (node (ref "MBED") (pin "1") (pinfunction "P$1_1") (pintype "bidirectional"))
      (node (ref "R10") (pin "1") (pinfunction "1_1") (pintype "passive"))
      (node (ref "R2") (pin "2") (pinfunction "2_2") (pintype "passive"))
      (node (ref "R26") (pin "1") (pinfunction "1_1") (pintype "passive"))
      (node (ref "R28") (pin "1") (pinfunction "1_1") (pintype "passive"))
      (node (ref "R31") (pin "1") (pinfunction "1_1") (pintype "passive"))
      (node (ref "R4") (pin "2") (pinfunction "2_2") (pintype "passive"))
      (node (ref "R6") (pin "2") (pinfunction "2_2") (pintype "passive"))
      (node (ref "R8") (pin "2") (pinfunction "2_2") (pintype "passive"))
      (node (ref "RPI_HEADER") (pin "14") (pinfunction "14_14") (pintype "passive"))
      (node (ref "RPI_HEADER") (pin "20") (pinfunction "20_20") (pintype "passive"))
      (node (ref "RPI_HEADER") (pin "25") (pinfunction "25_25") (pintype "passive"))
      (node (ref "RPI_HEADER") (pin "30") (pinfunction "30_30") (pintype "passive"))
      (node (ref "RPI_HEADER") (pin "34") (pinfunction "34_34") (pintype "passive"))
      (node (ref "RPI_HEADER") (pin "39") (pinfunction "39_39") (pintype "passive"))
      (node (ref "RPI_HEADER") (pin "6") (pinfunction "6_6") (pintype "passive"))
      (node (ref "RPI_HEADER") (pin "9") (pinfunction "9_9") (pintype "passive"))
      (node (ref "U$4") (pin "2") (pinfunction "2_2") (pintype "passive"))
      (node (ref "U$4") (pin "5") (pinfunction "5_5") (pintype "passive"))
      (node (ref "U$5") (pin "6") (pinfunction "6_6") (pintype "passive"))
      (node (ref "USB") (pin "5") (pinfunction "5_5") (pintype "bidirectional"))
    )
    (net (code "49") (name "Net-(ACS715_BCU-FILTER)") (class "Default")
      (node (ref "ACS715_BCU") (pin "6") (pinfunction "FILTER_6") (pintype "passive"))
      (node (ref "C11") (pin "1") (pinfunction "1_1") (pintype "passive"))
    )
    (net (code "50") (name "Net-(ACS715_BCU-VIOUT)") (class "Default")
      (node (ref "ACS715_BCU") (pin "7") (pinfunction "VIOUT_7") (pintype "output"))
      (node (ref "R24") (pin "1") (pinfunction "1_1") (pintype "passive"))
    )
    (net (code "51") (name "Net-(ACS715_VALVE-FILTER)") (class "Default")
      (node (ref "ACS715_VALVE") (pin "6") (pinfunction "FILTER_6") (pintype "passive"))
      (node (ref "C9") (pin "1") (pinfunction "1_1") (pintype "passive"))
    )
    (net (code "52") (name "Net-(ACS715_VALVE-VIOUT)") (class "Default")
      (node (ref "ACS715_VALVE") (pin "7") (pinfunction "VIOUT_7") (pintype "output"))
      (node (ref "R23") (pin "1") (pinfunction "1_1") (pintype "passive"))
    )
    (net (code "53") (name "Net-(D1-C)") (class "Default")
      (node (ref "D1") (pin "1") (pinfunction "C_1") (pintype "bidirectional"))
      (node (ref "LMZ1") (pin "3") (pinfunction "EN_3") (pintype "input"))
      (node (ref "R3") (pin "2") (pinfunction "2_2") (pintype "passive"))
      (node (ref "R4") (pin "1") (pinfunction "1_1") (pintype "passive"))
    )
    (net (code "54") (name "Net-(D2-C)") (class "Default")
      (node (ref "D2") (pin "1") (pinfunction "C_1") (pintype "bidirectional"))
      (node (ref "LMZ2") (pin "3") (pinfunction "EN_3") (pintype "input"))
      (node (ref "R7") (pin "2") (pinfunction "2_2") (pintype "passive"))
      (node (ref "R8") (pin "1") (pinfunction "1_1") (pintype "passive"))
    )
    (net (code "55") (name "Net-(DRV8835-MODE)") (class "Default")
      (node (ref "DRV8835") (pin "11") (pinfunction "MODE_11") (pintype "input"))
      (node (ref "R31") (pin "2") (pinfunction "2_2") (pintype "passive"))
    )
    (net (code "56") (name "Net-(DRV8838-NSLEEP)") (class "Default")
      (node (ref "DRV8838") (pin "7") (pinfunction "NSLEEP_7") (pintype "input"))
      (node (ref "R32") (pin "2") (pinfunction "2_2") (pintype "passive"))
    )
    (net (code "57") (name "Net-(LM1A--IN)") (class "Default")
      (node (ref "LM1") (pin "2") (pinfunction "-IN_2") (pintype "input"))
      (node (ref "R25") (pin "1") (pinfunction "1_1") (pintype "passive"))
      (node (ref "R26") (pin "2") (pinfunction "2_2") (pintype "passive"))
    )
    (net (code "58") (name "Net-(LM1B--IN)") (class "Default")
      (node (ref "LM1") (pin "6") (pinfunction "-IN_6") (pintype "input"))
      (node (ref "R27") (pin "1") (pinfunction "1_1") (pintype "passive"))
      (node (ref "R28") (pin "2") (pinfunction "2_2") (pintype "passive"))
    )
    (net (code "59") (name "Net-(LMZ1-FB)") (class "Default")
      (node (ref "LMZ1") (pin "5") (pinfunction "FB_5") (pintype "input"))
      (node (ref "R1") (pin "1") (pinfunction "1_1") (pintype "passive"))
      (node (ref "R2") (pin "1") (pinfunction "1_1") (pintype "passive"))
    )
    (net (code "60") (name "Net-(LMZ1-SS{slash}TRK)") (class "Default")
      (node (ref "C2") (pin "1") (pinfunction "1_1") (pintype "passive"))
      (node (ref "LMZ1") (pin "6") (pinfunction "SS/TRK_6") (pintype "bidirectional"))
    )
    (net (code "61") (name "Net-(LMZ2-FB)") (class "Default")
      (node (ref "LMZ2") (pin "5") (pinfunction "FB_5") (pintype "input"))
      (node (ref "R5") (pin "1") (pinfunction "1_1") (pintype "passive"))
      (node (ref "R6") (pin "1") (pinfunction "1_1") (pintype "passive"))
    )
    (net (code "62") (name "Net-(LMZ2-SS{slash}TRK)") (class "Default")
      (node (ref "C4") (pin "1") (pinfunction "1_1") (pintype "passive"))
      (node (ref "LMZ2") (pin "6") (pinfunction "SS/TRK_6") (pintype "bidirectional"))
    )
    (net (code "63") (name "Net-(MAX14870-~{FAULT})") (class "Default")
      (node (ref "MAX14870") (pin "7") (pinfunction "~{FAULT}_7") (pintype "passive"))
      (node (ref "NFAULT") (pin "TP") (pinfunction "TP_TP") (pintype "input"))
      (node (ref "R22") (pin "2") (pinfunction "2_2") (pintype "passive"))
    )
    (net (code "64") (name "Net-(MAX16052-CDELAY)") (class "Default")
      (node (ref "C6") (pin "1") (pinfunction "1_1") (pintype "passive"))
      (node (ref "MAX16052") (pin "6") (pinfunction "CDELAY_6") (pintype "input"))
    )
    (net (code "65") (name "Net-(MAX16052-IN)") (class "Default")
      (node (ref "MAX16052") (pin "3") (pinfunction "IN_3") (pintype "input"))
      (node (ref "R10") (pin "2") (pinfunction "2_2") (pintype "passive"))
      (node (ref "R9") (pin "2") (pinfunction "2_2") (pintype "passive"))
    )
    (net (code "66") (name "Net-(MBED-P$16)") (class "Default")
      (node (ref "MBED") (pin "16") (pinfunction "P$16_16") (pintype "bidirectional"))
      (node (ref "R19") (pin "2") (pinfunction "2_2") (pintype "passive"))
    )
    (net (code "67") (name "Net-(R12-Pad1)") (class "Default")
      (node (ref "R12") (pin "1") (pinfunction "1_1") (pintype "passive"))
      (node (ref "USB") (pin "4") (pinfunction "4_4") (pintype "bidirectional"))
    )
    (net (code "68") (name "Net-(R13-Pad1)") (class "Default")
      (node (ref "R13") (pin "1") (pinfunction "1_1") (pintype "passive"))
      (node (ref "USB") (pin "2") (pinfunction "2_2") (pintype "bidirectional"))
    )
    (net (code "69") (name "Net-(R20-Pad2)") (class "Default")
      (node (ref "R20") (pin "2") (pinfunction "2_2") (pintype "passive"))
      (node (ref "RPI_HEADER") (pin "29") (pinfunction "29_29") (pintype "passive"))
    )
    (net (code "70") (name "unconnected-(DRV8835-BIN1{slash}BPHASE-Pad8)") (class "Default")
      (node (ref "DRV8835") (pin "8") (pinfunction "BIN1/BPHASE_8") (pintype "input"))
    )
    (net (code "71") (name "unconnected-(DRV8835-BIN2{slash}BENBL-Pad7)") (class "Default")
      (node (ref "DRV8835") (pin "7") (pinfunction "BIN2/BENBL_7") (pintype "input"))
    )
    (net (code "72") (name "unconnected-(DRV8835-BOUT1-Pad4)") (class "Default")
      (node (ref "DRV8835") (pin "4") (pinfunction "BOUT1_4") (pintype "output"))
    )
    (net (code "73") (name "unconnected-(DRV8835-BOUT2-Pad5)") (class "Default")
      (node (ref "DRV8835") (pin "5") (pinfunction "BOUT2_5") (pintype "output"))
    )
    (net (code "74") (name "unconnected-(IMU_1-Pad4)") (class "Default")
      (node (ref "IMU_1") (pin "4") (pinfunction "4_4") (pintype "bidirectional"))
    )
    (net (code "75") (name "unconnected-(MBED-P$3-Pad3)") (class "Default")
      (node (ref "MBED") (pin "3") (pinfunction "P$3_3") (pintype "bidirectional"))
    )
    (net (code "76") (name "unconnected-(MBED-P$11-Pad11)") (class "Default")
      (node (ref "MBED") (pin "11") (pinfunction "P$11_11") (pintype "bidirectional"))
    )
    (net (code "77") (name "unconnected-(MBED-P$33-Pad33)") (class "Default")
      (node (ref "MBED") (pin "33") (pinfunction "P$33_33") (pintype "bidirectional"))
    )
    (net (code "78") (name "unconnected-(MBED-P$34-Pad34)") (class "Default")
      (node (ref "MBED") (pin "34") (pinfunction "P$34_34") (pintype "bidirectional"))
    )
    (net (code "79") (name "unconnected-(MBED-P$35-Pad35)") (class "Default")
      (node (ref "MBED") (pin "35") (pinfunction "P$35_35") (pintype "bidirectional"))
    )
    (net (code "80") (name "unconnected-(MBED-P$36-Pad36)") (class "Default")
      (node (ref "MBED") (pin "36") (pinfunction "P$36_36") (pintype "bidirectional"))
    )
    (net (code "81") (name "unconnected-(RPI_HEADER-Pad1)") (class "Default")
      (node (ref "RPI_HEADER") (pin "1") (pinfunction "1_1") (pintype "passive"))
    )
    (net (code "82") (name "unconnected-(RPI_HEADER-Pad3)") (class "Default")
      (node (ref "RPI_HEADER") (pin "3") (pinfunction "3_3") (pintype "passive"))
    )
    (net (code "83") (name "unconnected-(RPI_HEADER-Pad7)") (class "Default")
      (node (ref "RPI_HEADER") (pin "7") (pinfunction "7_7") (pintype "passive"))
    )
    (net (code "84") (name "unconnected-(RPI_HEADER-Pad11)") (class "Default")
      (node (ref "RPI_HEADER") (pin "11") (pinfunction "11_11") (pintype "passive"))
    )
    (net (code "85") (name "unconnected-(RPI_HEADER-Pad12)") (class "Default")
      (node (ref "RPI_HEADER") (pin "12") (pinfunction "12_12") (pintype "passive"))
    )
    (net (code "86") (name "unconnected-(RPI_HEADER-Pad13)") (class "Default")
      (node (ref "RPI_HEADER") (pin "13") (pinfunction "13_13") (pintype "passive"))
    )
    (net (code "87") (name "unconnected-(RPI_HEADER-Pad15)") (class "Default")
      (node (ref "RPI_HEADER") (pin "15") (pinfunction "15_15") (pintype "passive"))
    )
    (net (code "88") (name "unconnected-(RPI_HEADER-Pad16)") (class "Default")
      (node (ref "RPI_HEADER") (pin "16") (pinfunction "16_16") (pintype "passive"))
    )
    (net (code "89") (name "unconnected-(RPI_HEADER-Pad17)") (class "Default")
      (node (ref "RPI_HEADER") (pin "17") (pinfunction "17_17") (pintype "passive"))
    )
    (net (code "90") (name "unconnected-(RPI_HEADER-Pad18)") (class "Default")
      (node (ref "RPI_HEADER") (pin "18") (pinfunction "18_18") (pintype "passive"))
    )
    (net (code "91") (name "unconnected-(RPI_HEADER-Pad22)") (class "Default")
      (node (ref "RPI_HEADER") (pin "22") (pinfunction "22_22") (pintype "passive"))
    )
    (net (code "92") (name "unconnected-(RPI_HEADER-Pad26)") (class "Default")
      (node (ref "RPI_HEADER") (pin "26") (pinfunction "26_26") (pintype "passive"))
    )
    (net (code "93") (name "unconnected-(RPI_HEADER-Pad27)") (class "Default")
      (node (ref "RPI_HEADER") (pin "27") (pinfunction "27_27") (pintype "passive"))
    )
    (net (code "94") (name "unconnected-(RPI_HEADER-Pad28)") (class "Default")
      (node (ref "RPI_HEADER") (pin "28") (pinfunction "28_28") (pintype "passive"))
    )
    (net (code "95") (name "unconnected-(RPI_HEADER-Pad31)") (class "Default")
      (node (ref "RPI_HEADER") (pin "31") (pinfunction "31_31") (pintype "passive"))
    )
    (net (code "96") (name "unconnected-(RPI_HEADER-Pad32)") (class "Default")
      (node (ref "RPI_HEADER") (pin "32") (pinfunction "32_32") (pintype "passive"))
    )
    (net (code "97") (name "unconnected-(RPI_HEADER-Pad33)") (class "Default")
      (node (ref "RPI_HEADER") (pin "33") (pinfunction "33_33") (pintype "passive"))
    )
    (net (code "98") (name "unconnected-(RPI_HEADER-Pad35)") (class "Default")
      (node (ref "RPI_HEADER") (pin "35") (pinfunction "35_35") (pintype "passive"))
    )
    (net (code "99") (name "unconnected-(RPI_HEADER-Pad36)") (class "Default")
      (node (ref "RPI_HEADER") (pin "36") (pinfunction "36_36") (pintype "passive"))
    )
    (net (code "100") (name "unconnected-(RPI_HEADER-Pad37)") (class "Default")
      (node (ref "RPI_HEADER") (pin "37") (pinfunction "37_37") (pintype "passive"))
    )
    (net (code "101") (name "unconnected-(RPI_HEADER-Pad38)") (class "Default")
      (node (ref "RPI_HEADER") (pin "38") (pinfunction "38_38") (pintype "passive"))
    )
    (net (code "102") (name "unconnected-(RPI_HEADER-Pad40)") (class "Default")
      (node (ref "RPI_HEADER") (pin "40") (pinfunction "40_40") (pintype "passive"))
    )
    (net (code "103") (name "unconnected-(U$4-Pad1)") (class "Default")
      (node (ref "U$4") (pin "1") (pinfunction "1_1") (pintype "passive"))
    )
    (net (code "104") (name "unconnected-(USB-Pad3)") (class "Default")
      (node (ref "USB") (pin "3") (pinfunction "3_3") (pintype "bidirectional"))
    )
    (net (code "105") (name "unconnected-(USB-Pad6)") (class "Default")
      (node (ref "USB") (pin "6") (pinfunction "6_6") (pintype "bidirectional"))
    )
  )
)
